# Main.net
KiCad netlist of a schematic drawn in Altium Designer
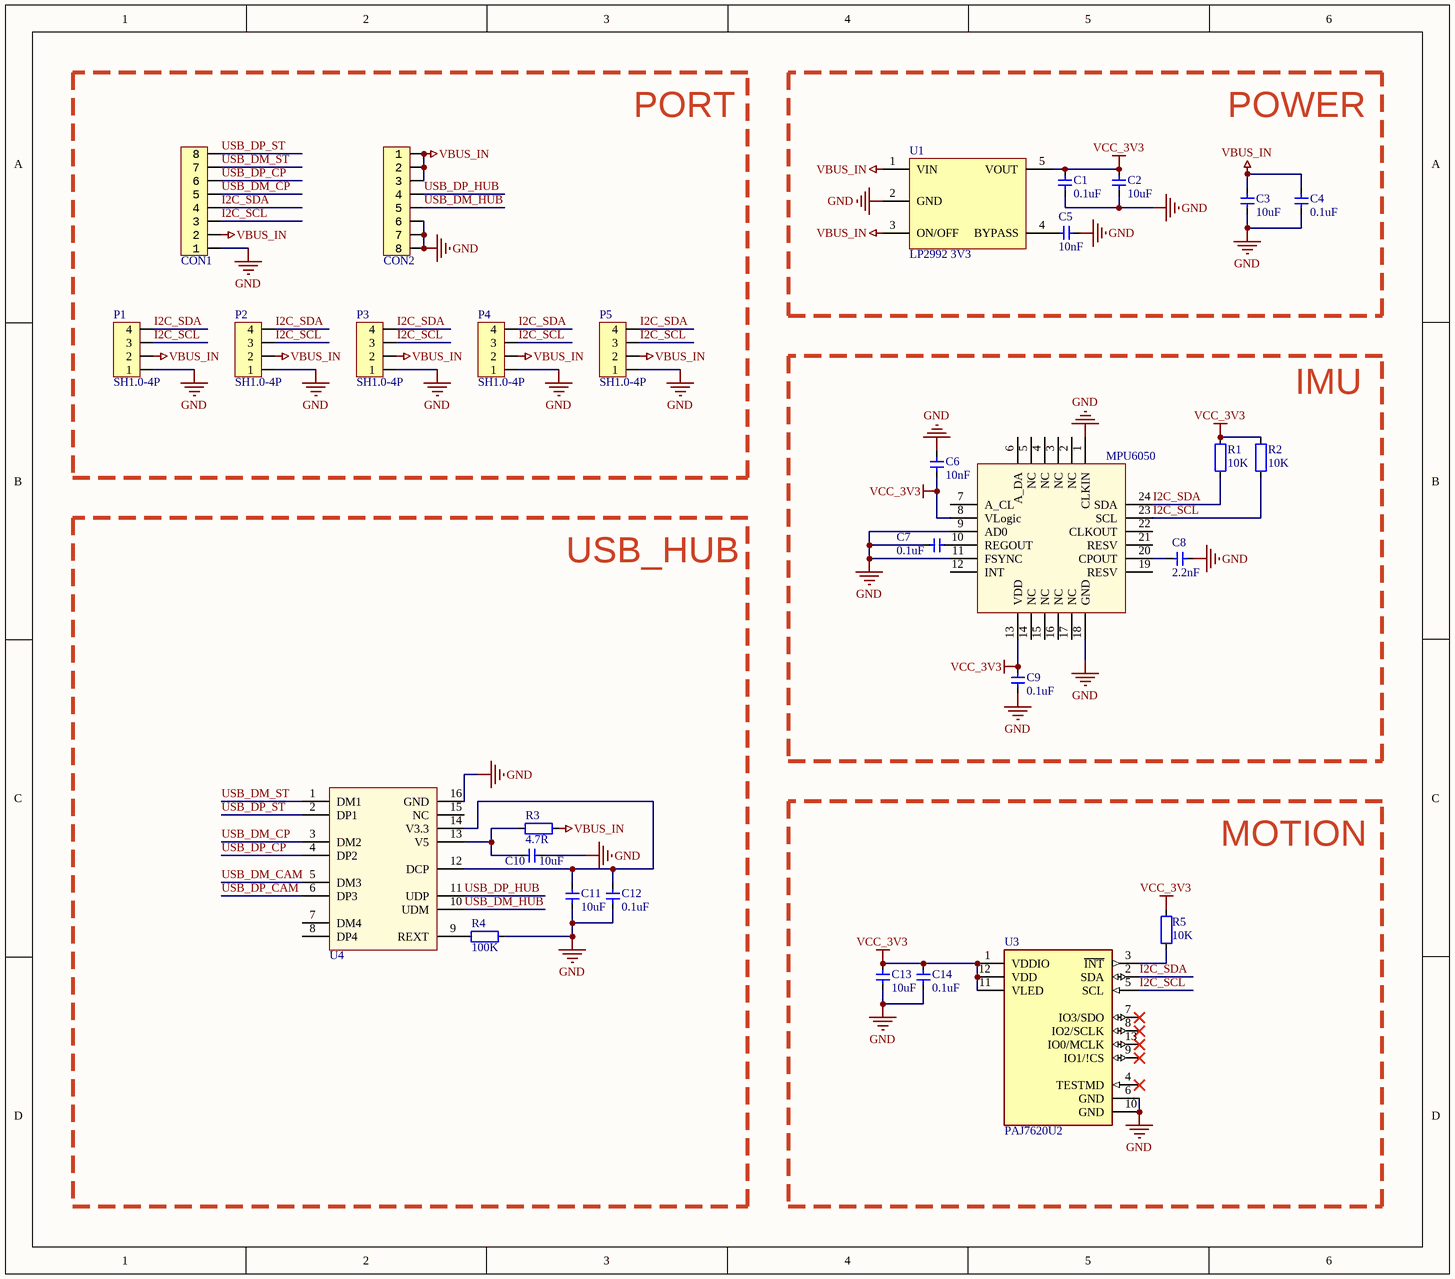
[diagram p0: Main.SchDoc]

(export (version "E")
  (design (tool "Eeschema 10.0.6"))
  (components
    (comp (ref "C1")
      (value "0.1uF")
      (footprint "CAP_0402")
      (description "Capacitor")
      (libsource (lib "MyPcbLib") (part "电容-0402"))
    )
    (comp (ref "C2")
      (value "10uF")
      (footprint "CAP_0402")
      (description "Capacitor")
      (libsource (lib "MyPcbLib") (part "电容-0402"))
    )
    (comp (ref "C3")
      (value "10uF")
      (footprint "CAP_0402")
      (description "Capacitor")
      (libsource (lib "MyPcbLib") (part "电容-0402"))
    )
    (comp (ref "C4")
      (value "0.1uF")
      (footprint "CAP_0402")
      (description "Capacitor")
      (libsource (lib "MyPcbLib") (part "电容-0402"))
    )
    (comp (ref "C5")
      (value "10nF")
      (footprint "CAP_0402")
      (description "Capacitor")
      (libsource (lib "MyPcbLib") (part "电容-0402"))
    )
    (comp (ref "C6")
      (value "10nF")
      (footprint "CAP_0402")
      (description "Capacitor")
      (libsource (lib "MyPcbLib") (part "电容-0402"))
    )
    (comp (ref "C7")
      (value "0.1uF")
      (footprint "CAP_0402")
      (description "Capacitor")
      (libsource (lib "MyPcbLib") (part "电容-0402"))
    )
    (comp (ref "C8")
      (value "2.2nF")
      (footprint "CAP_0402")
      (description "Capacitor")
      (libsource (lib "MyPcbLib") (part "电容-0402"))
    )
    (comp (ref "C9")
      (value "0.1uF")
      (footprint "CAP_0402")
      (description "Capacitor")
      (libsource (lib "MyPcbLib") (part "电容-0402"))
    )
    (comp (ref "C10")
      (value "10uF")
      (footprint "CAP_0402")
      (description "Capacitor")
      (libsource (lib "MyPcbLib") (part "电容-0402"))
    )
    (comp (ref "C11")
      (value "10uF")
      (footprint "CAP_0402")
      (description "Capacitor")
      (libsource (lib "MyPcbLib") (part "电容-0402"))
    )
    (comp (ref "C12")
      (value "0.1uF")
      (footprint "CAP_0402")
      (description "Capacitor")
      (libsource (lib "MyPcbLib") (part "电容-0402"))
    )
    (comp (ref "C13")
      (value "10uF")
      (footprint "CAP_0402")
      (description "Capacitor")
      (libsource (lib "MyPcbLib") (part "电容-0402"))
    )
    (comp (ref "C14")
      (value "0.1uF")
      (footprint "CAP_0402")
      (description "Capacitor")
      (libsource (lib "MyPcbLib") (part "电容-0402"))
    )
    (comp (ref "CON1")
      (value "FFC_0.5_8")
      (footprint "FFC_0.5_8")
      (description "FFC")
      (libsource (lib "") (part "FFC_0.5_8_1"))
    )
    (comp (ref "CON2")
      (value "FFC_0.5_8")
      (footprint "FFC_0.5_8")
      (description "FFC")
      (libsource (lib "KitSprout") (part "FFC_0.5_8"))
    )
    (comp (ref "P1") (value "SH1.0-4P") (footprint "SH1.0-4P") (libsource (lib "MyPcbLib") (part "SH1.0-4P")))
    (comp (ref "P2") (value "SH1.0-4P") (footprint "SH1.0-4P") (libsource (lib "MyPcbLib") (part "SH1.0-4P")))
    (comp (ref "P3") (value "SH1.0-4P") (footprint "SH1.0-4P") (libsource (lib "MyPcbLib") (part "SH1.0-4P")))
    (comp (ref "P4") (value "SH1.0-4P") (footprint "SH1.0-4P") (libsource (lib "MyPcbLib") (part "SH1.0-4P")))
    (comp (ref "P5") (value "SH1.0-4P") (footprint "SH1.0-4P") (libsource (lib "MyPcbLib") (part "SH1.0-4P")))
    (comp (ref "R1")
      (value "10K")
      (footprint "RES_0402")
      (description "Resistor")
      (libsource (lib "MyPcbLib") (part "电阻-0402"))
    )
    (comp (ref "R2")
      (value "10K")
      (footprint "RES_0402")
      (description "Resistor")
      (libsource (lib "MyPcbLib") (part "电阻-0402"))
    )
    (comp (ref "R3")
      (value "4.7R")
      (footprint "RES_0402")
      (description "Resistor")
      (libsource (lib "") (part "电阻-0402_2"))
    )
    (comp (ref "R4")
      (value "100K")
      (footprint "RES_0402")
      (description "Resistor")
      (libsource (lib "") (part "电阻-0402_2"))
    )
    (comp (ref "R5")
      (value "10K")
      (footprint "RES_0402")
      (description "Resistor")
      (libsource (lib "") (part "电阻-0402_1"))
    )
    (comp (ref "U1")
      (value "LP2992 3V3")
      (footprint "SOT23-5")
      (description "LDO")
      (libsource (lib "MyPcbLib") (part "LP2992"))
    )
    (comp (ref "U2")
      (value "MPU6050")
      (footprint "QFN-24")
      (description "六轴传感器")
      (libsource (lib "mLib") (part "MPU6050"))
    )
    (comp (ref "U3")
      (value "PAJ7620U2")
      (footprint "PAJ7620U2")
      (description "module sensorPAJ7620U2 : 54/TRAY, 5400/BOX, 32400/CARTON")
      (fields (field (name "MF") "Pixart"))
      (libsource (lib "MyPcbLib") (part "PAJ7620U2"))
    )
    (comp (ref "U4")
      (value "HS8836A")
      (footprint "SO-16N")
      (description "USB2.0 HUB")
      (libsource (lib "MyPcbLib") (part "HS8836A"))
    )
  )
  (nets
    (net (code "1") (name "/I2C_SCL") (class "Default")
      (node (ref "CON1") (pin "3") (pinfunction "3_3") (pintype "passive"))
      (node (ref "P1") (pin "3") (pinfunction "3_3") (pintype "passive"))
      (node (ref "P2") (pin "3") (pinfunction "3_3") (pintype "passive"))
      (node (ref "P3") (pin "3") (pinfunction "3_3") (pintype "passive"))
      (node (ref "P4") (pin "3") (pinfunction "3_3") (pintype "passive"))
      (node (ref "P5") (pin "3") (pinfunction "3_3") (pintype "passive"))
      (node (ref "R2") (pin "1") (pinfunction "1_1") (pintype "passive"))
      (node (ref "U2") (pin "23") (pinfunction "SCL_23") (pintype "passive"))
      (node (ref "U3") (pin "5") (pinfunction "SCL_5") (pintype "input"))
    )
    (net (code "2") (name "/I2C_SDA") (class "Default")
      (node (ref "CON1") (pin "4") (pinfunction "4_4") (pintype "passive"))
      (node (ref "P1") (pin "4") (pinfunction "4_4") (pintype "passive"))
      (node (ref "P2") (pin "4") (pinfunction "4_4") (pintype "passive"))
      (node (ref "P3") (pin "4") (pinfunction "4_4") (pintype "passive"))
      (node (ref "P4") (pin "4") (pinfunction "4_4") (pintype "passive"))
      (node (ref "P5") (pin "4") (pinfunction "4_4") (pintype "passive"))
      (node (ref "R1") (pin "1") (pinfunction "1_1") (pintype "passive"))
      (node (ref "U2") (pin "24") (pinfunction "SDA_24") (pintype "passive"))
      (node (ref "U3") (pin "2") (pinfunction "SDA_2") (pintype "bidirectional"))
    )
    (net (code "3") (name "/USB_DM_CAM") (class "Default")
      (node (ref "U4") (pin "5") (pinfunction "DM3_5") (pintype "passive"))
    )
    (net (code "4") (name "/USB_DM_CP") (class "Default")
      (node (ref "CON1") (pin "5") (pinfunction "5_5") (pintype "passive"))
      (node (ref "U4") (pin "3") (pinfunction "DM2_3") (pintype "passive"))
    )
    (net (code "5") (name "/USB_DM_HUB") (class "Default")
      (node (ref "CON2") (pin "5") (pinfunction "5_5") (pintype "passive"))
      (node (ref "U4") (pin "10") (pinfunction "UDM_10") (pintype "passive"))
    )
    (net (code "6") (name "/USB_DM_ST") (class "Default")
      (node (ref "CON1") (pin "7") (pinfunction "7_7") (pintype "passive"))
      (node (ref "U4") (pin "1") (pinfunction "DM1_1") (pintype "passive"))
    )
    (net (code "7") (name "/USB_DP_CAM") (class "Default")
      (node (ref "U4") (pin "6") (pinfunction "DP3_6") (pintype "passive"))
    )
    (net (code "8") (name "/USB_DP_CP") (class "Default")
      (node (ref "CON1") (pin "6") (pinfunction "6_6") (pintype "passive"))
      (node (ref "U4") (pin "4") (pinfunction "DP2_4") (pintype "passive"))
    )
    (net (code "9") (name "/USB_DP_HUB") (class "Default")
      (node (ref "CON2") (pin "4") (pinfunction "4_4") (pintype "passive"))
      (node (ref "U4") (pin "11") (pinfunction "UDP_11") (pintype "passive"))
    )
    (net (code "10") (name "/USB_DP_ST") (class "Default")
      (node (ref "CON1") (pin "8") (pinfunction "8_8") (pintype "passive"))
      (node (ref "U4") (pin "2") (pinfunction "DP1_2") (pintype "passive"))
    )
    (net (code "11") (name "GND") (class "Default")
      (node (ref "C1") (pin "1") (pinfunction "1_1") (pintype "passive"))
      (node (ref "C10") (pin "1") (pinfunction "1_1") (pintype "passive"))
      (node (ref "C11") (pin "2") (pinfunction "2_2") (pintype "passive"))
      (node (ref "C12") (pin "2") (pinfunction "2_2") (pintype "passive"))
      (node (ref "C13") (pin "2") (pinfunction "2_2") (pintype "passive"))
      (node (ref "C14") (pin "2") (pinfunction "2_2") (pintype "passive"))
      (node (ref "C2") (pin "1") (pinfunction "1_1") (pintype "passive"))
      (node (ref "C3") (pin "1") (pinfunction "1_1") (pintype "passive"))
      (node (ref "C4") (pin "1") (pinfunction "1_1") (pintype "passive"))
      (node (ref "C5") (pin "1") (pinfunction "1_1") (pintype "passive"))
      (node (ref "C6") (pin "2") (pinfunction "2_2") (pintype "passive"))
      (node (ref "C7") (pin "2") (pinfunction "2_2") (pintype "passive"))
      (node (ref "C8") (pin "1") (pinfunction "1_1") (pintype "passive"))
      (node (ref "C9") (pin "1") (pinfunction "1_1") (pintype "passive"))
      (node (ref "CON1") (pin "1") (pinfunction "1_1") (pintype "passive"))
      (node (ref "CON2") (pin "6") (pinfunction "6_6") (pintype "passive"))
      (node (ref "CON2") (pin "7") (pinfunction "7_7") (pintype "passive"))
      (node (ref "CON2") (pin "8") (pinfunction "8_8") (pintype "passive"))
      (node (ref "P1") (pin "1") (pinfunction "1_1") (pintype "passive"))
      (node (ref "P2") (pin "1") (pinfunction "1_1") (pintype "passive"))
      (node (ref "P3") (pin "1") (pinfunction "1_1") (pintype "passive"))
      (node (ref "P4") (pin "1") (pinfunction "1_1") (pintype "passive"))
      (node (ref "P5") (pin "1") (pinfunction "1_1") (pintype "passive"))
      (node (ref "R4") (pin "1") (pinfunction "1_1") (pintype "passive"))
      (node (ref "U1") (pin "2") (pinfunction "GND_2") (pintype "passive"))
      (node (ref "U2") (pin "1") (pinfunction "CLKIN_1") (pintype "passive"))
      (node (ref "U2") (pin "11") (pinfunction "FSYNC_11") (pintype "passive"))
      (node (ref "U2") (pin "18") (pinfunction "GND_18") (pintype "passive"))
      (node (ref "U2") (pin "9") (pinfunction "AD0_9") (pintype "passive"))
      (node (ref "U3") (pin "10") (pinfunction "GND_10") (pintype "passive"))
      (node (ref "U3") (pin "6") (pinfunction "GND_6") (pintype "passive"))
      (node (ref "U4") (pin "16") (pinfunction "GND_16") (pintype "passive"))
    )
    (net (code "12") (name "Net-(U1-BYPASS)") (class "Default")
      (node (ref "C5") (pin "2") (pinfunction "2_2") (pintype "passive"))
      (node (ref "U1") (pin "4") (pinfunction "BYPASS_4") (pintype "passive"))
    )
    (net (code "13") (name "Net-(U2-CPOUT)") (class "Default")
      (node (ref "C8") (pin "2") (pinfunction "2_2") (pintype "passive"))
      (node (ref "U2") (pin "20") (pinfunction "CPOUT_20") (pintype "passive"))
    )
    (net (code "14") (name "Net-(U2-REGOUT)") (class "Default")
      (node (ref "C7") (pin "1") (pinfunction "1_1") (pintype "passive"))
      (node (ref "U2") (pin "10") (pinfunction "REGOUT_10") (pintype "passive"))
    )
    (net (code "15") (name "Net-(U3-~{INT})") (class "Default")
      (node (ref "R5") (pin "2") (pinfunction "2_2") (pintype "passive"))
      (node (ref "U3") (pin "3") (pinfunction "~{INT}_3") (pintype "output"))
    )
    (net (code "16") (name "Net-(U4-DCP)") (class "Default")
      (node (ref "C11") (pin "1") (pinfunction "1_1") (pintype "passive"))
      (node (ref "C12") (pin "1") (pinfunction "1_1") (pintype "passive"))
      (node (ref "U4") (pin "12") (pinfunction "DCP_12") (pintype "passive"))
      (node (ref "U4") (pin "14") (pinfunction "V3.3_14") (pintype "passive"))
    )
    (net (code "17") (name "Net-(U4-REXT)") (class "Default")
      (node (ref "R4") (pin "2") (pinfunction "2_2") (pintype "passive"))
      (node (ref "U4") (pin "9") (pinfunction "REXT_9") (pintype "passive"))
    )
    (net (code "18") (name "Net-(U4-V5)") (class "Default")
      (node (ref "C10") (pin "2") (pinfunction "2_2") (pintype "passive"))
      (node (ref "R3") (pin "2") (pinfunction "2_2") (pintype "passive"))
      (node (ref "U4") (pin "13") (pinfunction "V5_13") (pintype "passive"))
    )
    (net (code "19") (name "VBUS_IN") (class "Default")
      (node (ref "C3") (pin "2") (pinfunction "2_2") (pintype "passive"))
      (node (ref "C4") (pin "2") (pinfunction "2_2") (pintype "passive"))
      (node (ref "CON1") (pin "2") (pinfunction "2_2") (pintype "passive"))
      (node (ref "CON2") (pin "1") (pinfunction "1_1") (pintype "passive"))
      (node (ref "CON2") (pin "2") (pinfunction "2_2") (pintype "passive"))
      (node (ref "CON2") (pin "3") (pinfunction "3_3") (pintype "passive"))
      (node (ref "P1") (pin "2") (pinfunction "2_2") (pintype "passive"))
      (node (ref "P2") (pin "2") (pinfunction "2_2") (pintype "passive"))
      (node (ref "P3") (pin "2") (pinfunction "2_2") (pintype "passive"))
      (node (ref "P4") (pin "2") (pinfunction "2_2") (pintype "passive"))
      (node (ref "P5") (pin "2") (pinfunction "2_2") (pintype "passive"))
      (node (ref "R3") (pin "1") (pinfunction "1_1") (pintype "passive"))
      (node (ref "U1") (pin "1") (pinfunction "VIN_1") (pintype "passive"))
      (node (ref "U1") (pin "3") (pinfunction "ON/OFF_3") (pintype "passive"))
    )
    (net (code "20") (name "VCC_3V3") (class "Default")
      (node (ref "C1") (pin "2") (pinfunction "2_2") (pintype "passive"))
      (node (ref "C13") (pin "1") (pinfunction "1_1") (pintype "passive"))
      (node (ref "C14") (pin "1") (pinfunction "1_1") (pintype "passive"))
      (node (ref "C2") (pin "2") (pinfunction "2_2") (pintype "passive"))
      (node (ref "C6") (pin "1") (pinfunction "1_1") (pintype "passive"))
      (node (ref "C9") (pin "2") (pinfunction "2_2") (pintype "passive"))
      (node (ref "R1") (pin "2") (pinfunction "2_2") (pintype "passive"))
      (node (ref "R2") (pin "2") (pinfunction "2_2") (pintype "passive"))
      (node (ref "R5") (pin "1") (pinfunction "1_1") (pintype "passive"))
      (node (ref "U1") (pin "5") (pinfunction "VOUT_5") (pintype "passive"))
      (node (ref "U2") (pin "13") (pinfunction "VDD_13") (pintype "passive"))
      (node (ref "U2") (pin "8") (pinfunction "VLogic_8") (pintype "passive"))
      (node (ref "U3") (pin "1") (pinfunction "VDDIO_1") (pintype "power_in"))
      (node (ref "U3") (pin "11") (pinfunction "VLED_11") (pintype "power_in"))
      (node (ref "U3") (pin "12") (pinfunction "VDD_12") (pintype "power_in"))
    )
    (net (code "21") (name "unconnected-(U2-A_CL-Pad7)") (class "Default")
      (node (ref "U2") (pin "7") (pinfunction "A_CL_7") (pintype "passive"))
    )
    (net (code "22") (name "unconnected-(U2-A_DA-Pad6)") (class "Default")
      (node (ref "U2") (pin "6") (pinfunction "A_DA_6") (pintype "passive"))
    )
    (net (code "23") (name "unconnected-(U2-CLKOUT-Pad22)") (class "Default")
      (node (ref "U2") (pin "22") (pinfunction "CLKOUT_22") (pintype "passive"))
    )
    (net (code "24") (name "unconnected-(U2-INT-Pad12)") (class "Default")
      (node (ref "U2") (pin "12") (pinfunction "INT_12") (pintype "passive"))
    )
    (net (code "25") (name "unconnected-(U2-NC-Pad2)") (class "Default")
      (node (ref "U2") (pin "2") (pinfunction "NC_2") (pintype "passive"))
    )
    (net (code "26") (name "unconnected-(U2-NC-Pad3)") (class "Default")
      (node (ref "U2") (pin "3") (pinfunction "NC_3") (pintype "passive"))
    )
    (net (code "27") (name "unconnected-(U2-NC-Pad4)") (class "Default")
      (node (ref "U2") (pin "4") (pinfunction "NC_4") (pintype "passive"))
    )
    (net (code "28") (name "unconnected-(U2-NC-Pad5)") (class "Default")
      (node (ref "U2") (pin "5") (pinfunction "NC_5") (pintype "passive"))
    )
    (net (code "29") (name "unconnected-(U2-NC-Pad14)") (class "Default")
      (node (ref "U2") (pin "14") (pinfunction "NC_14") (pintype "passive"))
    )
    (net (code "30") (name "unconnected-(U2-NC-Pad15)") (class "Default")
      (node (ref "U2") (pin "15") (pinfunction "NC_15") (pintype "passive"))
    )
    (net (code "31") (name "unconnected-(U2-NC-Pad16)") (class "Default")
      (node (ref "U2") (pin "16") (pinfunction "NC_16") (pintype "passive"))
    )
    (net (code "32") (name "unconnected-(U2-NC-Pad17)") (class "Default")
      (node (ref "U2") (pin "17") (pinfunction "NC_17") (pintype "passive"))
    )
    (net (code "33") (name "unconnected-(U2-RESV-Pad19)") (class "Default")
      (node (ref "U2") (pin "19") (pinfunction "RESV_19") (pintype "passive"))
    )
    (net (code "34") (name "unconnected-(U2-RESV-Pad21)") (class "Default")
      (node (ref "U2") (pin "21") (pinfunction "RESV_21") (pintype "passive"))
    )
    (net (code "35") (name "unconnected-(U3-IO0{slash}MCLK-Pad13)") (class "Default")
      (node (ref "U3") (pin "13") (pinfunction "IO0/MCLK_13") (pintype "bidirectional+no_connect"))
    )
    (net (code "36") (name "unconnected-(U3-IO1{slash}!CS-Pad9)") (class "Default")
      (node (ref "U3") (pin "9") (pinfunction "IO1/!CS_9") (pintype "bidirectional+no_connect"))
    )
    (net (code "37") (name "unconnected-(U3-IO2{slash}SCLK-Pad8)") (class "Default")
      (node (ref "U3") (pin "8") (pinfunction "IO2/SCLK_8") (pintype "bidirectional+no_connect"))
    )
    (net (code "38") (name "unconnected-(U3-IO3{slash}SDO-Pad7)") (class "Default")
      (node (ref "U3") (pin "7") (pinfunction "IO3/SDO_7") (pintype "bidirectional+no_connect"))
    )
    (net (code "39") (name "unconnected-(U3-TESTMD-Pad4)") (class "Default")
      (node (ref "U3") (pin "4") (pinfunction "TESTMD_4") (pintype "input+no_connect"))
    )
    (net (code "40") (name "unconnected-(U4-DM4-Pad7)") (class "Default")
      (node (ref "U4") (pin "7") (pinfunction "DM4_7") (pintype "passive"))
    )
    (net (code "41") (name "unconnected-(U4-DP4-Pad8)") (class "Default")
      (node (ref "U4") (pin "8") (pinfunction "DP4_8") (pintype "passive"))
    )
    (net (code "42") (name "unconnected-(U4-NC-Pad15)") (class "Default")
      (node (ref "U4") (pin "15") (pinfunction "NC_15") (pintype "passive"))
    )
  )
)
